# MB128_tester_PCB.net
KiCad netlist of a schematic drawn in EAGLE
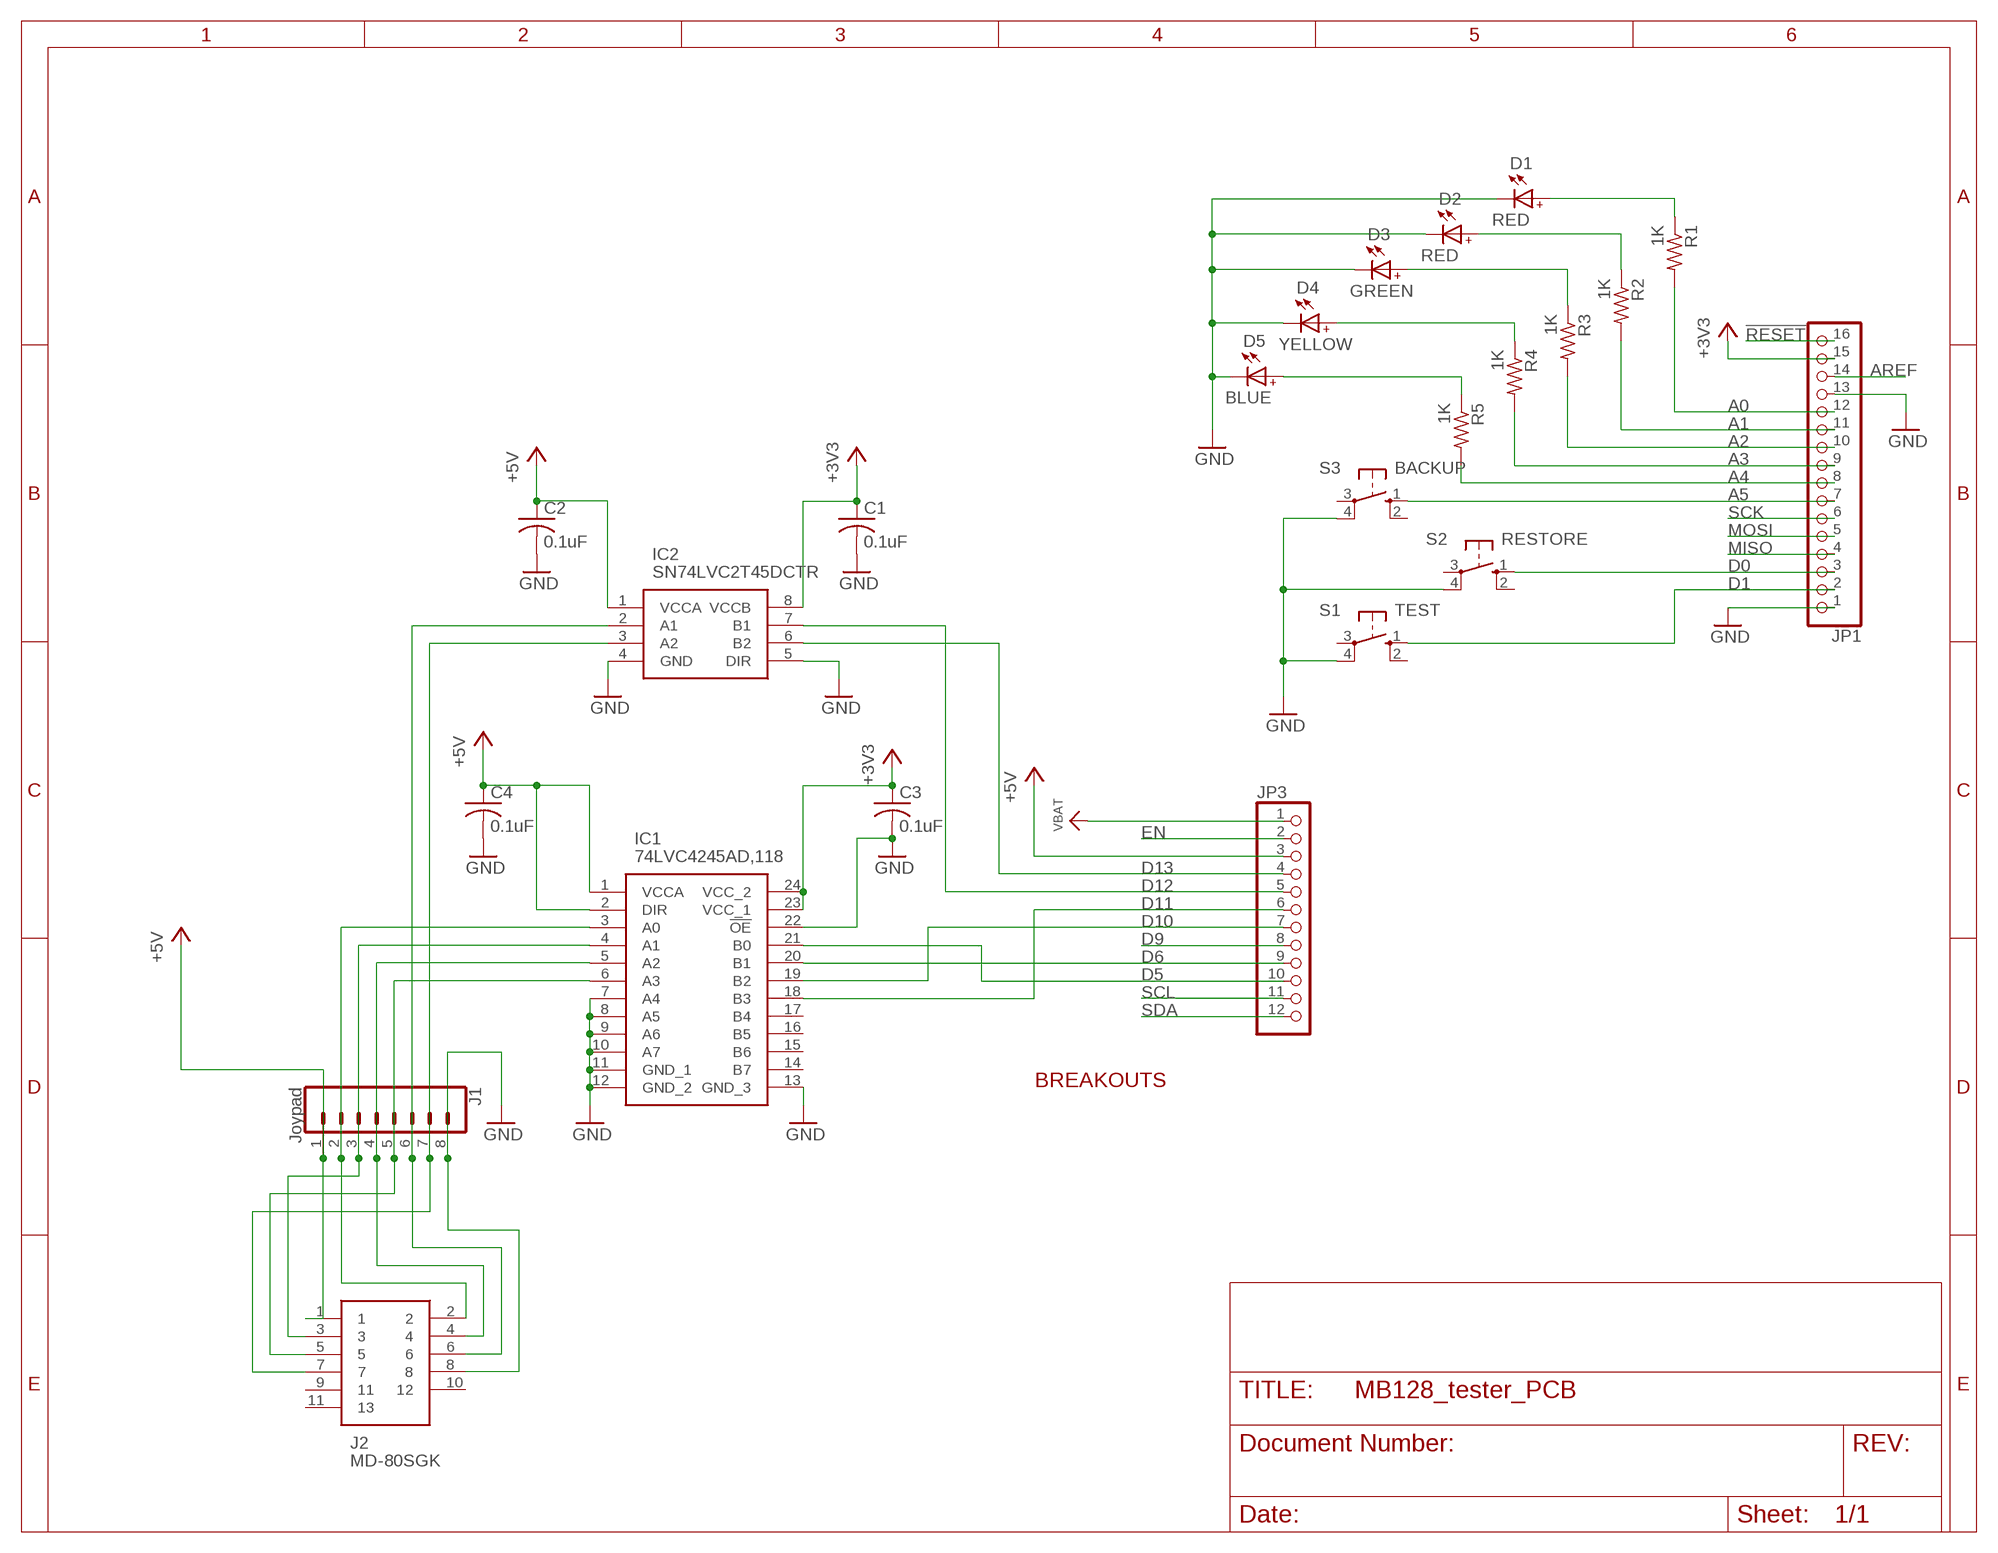
[diagram p0: schematic, sheet 1]

(export (version "E")
  (design (tool "Eeschema 10.0.6"))
  (components
    (comp (ref "C1")
      (value "0.1uF")
      (footprint "eagle-import:C0805")
      (libsource (lib "eagle-import") (part "C-USC0805"))
    )
    (comp (ref "C2")
      (value "0.1uF")
      (footprint "eagle-import:C0805")
      (libsource (lib "eagle-import") (part "C-USC0805"))
    )
    (comp (ref "C3")
      (value "0.1uF")
      (footprint "eagle-import:C0805")
      (libsource (lib "eagle-import") (part "C-USC0805"))
    )
    (comp (ref "C4")
      (value "0.1uF")
      (footprint "eagle-import:C0805")
      (libsource (lib "eagle-import") (part "C-USC0805"))
    )
    (comp (ref "D1")
      (value "RED")
      (footprint "eagle-import:WL-SMCC_0603_R_Y_V")
      (libsource (lib "eagle-import") (part "WL-SMCC_0603_R/V/Y_150060RS73220"))
    )
    (comp (ref "D2")
      (value "RED")
      (footprint "eagle-import:WL-SMCC_0603_R_Y_V")
      (libsource (lib "eagle-import") (part "WL-SMCC_0603_R/V/Y_150060RS73220"))
    )
    (comp (ref "D3")
      (value "GREEN")
      (footprint "eagle-import:WL-SMCC_0603_R_Y_V")
      (libsource (lib "eagle-import") (part "WL-SMCC_0603_R/V/Y_150060RS73220"))
    )
    (comp (ref "D4")
      (value "YELLOW")
      (footprint "eagle-import:WL-SMCC_0603_R_Y_V")
      (libsource (lib "eagle-import") (part "WL-SMCC_0603_R/V/Y_150060RS73220"))
    )
    (comp (ref "D5")
      (value "BLUE")
      (footprint "eagle-import:WL-SMCC_0603_R_Y_V")
      (libsource (lib "eagle-import") (part "WL-SMCC_0603_R/V/Y_150060RS73220"))
    )
    (comp (ref "IC1")
      (value "74LVC4245AD,118")
      (footprint "eagle-import:SOIC127P1032X265-24N")
      (fields
        (field (name "MOUSER_PART_NUMBER") "771-74LVC4245AD-T")
        (field (name "RS_PART_NUMBER") "1708039")
      )
      (libsource (lib "eagle-import") (part "74LVC4245AD,118"))
    )
    (comp (ref "IC2")
      (value "SN74LVC2T45DCTR")
      (footprint "eagle-import:SOP65P400X130-8N")
      (fields
        (field (name "MOUSER_PART_NUMBER") "595-SN74LVC2T45DCTR")
        (field (name "RS_PART_NUMBER") "9213022")
      )
      (libsource (lib "eagle-import") (part "SN74LVC2T45DCTR"))
    )
    (comp (ref "J1")
      (value "Joypad")
      (footprint "eagle-import:1X08")
      (libsource (lib "eagle-import") (part "CONN_08{dblquote}"))
    )
    (comp (ref "J2")
      (value "MD-80SGK")
      (footprint "eagle-import:MD80SGK")
      (fields (field (name "MOUSER_PART_NUMBER") "490-MD-80SGK"))
      (libsource (lib "eagle-import") (part "MD-80SGK"))
    )
    (comp (ref "JP1")
      (value "HEADER-1X16ROUND")
      (footprint "eagle-import:1X16_ROUND")
      (libsource (lib "eagle-import") (part "HEADER-1X16ROUND"))
    )
    (comp (ref "JP3")
      (value "HEADER-1X12")
      (footprint "eagle-import:1X12_ROUND")
      (libsource (lib "eagle-import") (part "HEADER-1X12"))
    )
    (comp (ref "R1")
      (value "1K")
      (footprint "eagle-import:R0603")
      (libsource (lib "eagle-import") (part "R-US_R0603"))
    )
    (comp (ref "R2")
      (value "1K")
      (footprint "eagle-import:R0603")
      (libsource (lib "eagle-import") (part "R-US_R0603"))
    )
    (comp (ref "R3")
      (value "1K")
      (footprint "eagle-import:R0603")
      (libsource (lib "eagle-import") (part "R-US_R0603"))
    )
    (comp (ref "R4")
      (value "1K")
      (footprint "eagle-import:R0603")
      (libsource (lib "eagle-import") (part "R-US_R0603"))
    )
    (comp (ref "R5")
      (value "1K")
      (footprint "eagle-import:R0603")
      (libsource (lib "eagle-import") (part "R-US_R0603"))
    )
    (comp (ref "S1")
      (value "TEST")
      (footprint "eagle-import:B3F-10XX")
      (fields (field (name "MPN") "B3F-1000"))
      (libsource (lib "eagle-import") (part "10-XX"))
    )
    (comp (ref "S2")
      (value "RESTORE")
      (footprint "eagle-import:B3F-10XX")
      (fields (field (name "MPN") "B3F-1000"))
      (libsource (lib "eagle-import") (part "10-XX"))
    )
    (comp (ref "S3")
      (value "BACKUP")
      (footprint "eagle-import:B3F-10XX")
      (fields (field (name "MPN") "B3F-1000"))
      (libsource (lib "eagle-import") (part "10-XX"))
    )
  )
  (nets
    (net (code "1") (name "+3V3") (class "Default")
      (node (ref "C1") (pin "1") (pinfunction "1_1") (pintype "passive"))
      (node (ref "C3") (pin "1") (pinfunction "1_1") (pintype "passive"))
      (node (ref "IC1") (pin "23") (pinfunction "VCC_1_23") (pintype "bidirectional"))
      (node (ref "IC1") (pin "24") (pinfunction "VCC_2_24") (pintype "bidirectional"))
      (node (ref "IC2") (pin "8") (pinfunction "VCCB_8") (pintype "power_in"))
      (node (ref "JP1") (pin "15") (pinfunction "15_15") (pintype "passive"))
    )
    (net (code "2") (name "+5V") (class "Default")
      (node (ref "C2") (pin "1") (pinfunction "1_1") (pintype "passive"))
      (node (ref "C4") (pin "1") (pinfunction "1_1") (pintype "passive"))
      (node (ref "IC1") (pin "1") (pinfunction "VCCA_1") (pintype "bidirectional"))
      (node (ref "IC1") (pin "2") (pinfunction "DIR_2") (pintype "bidirectional"))
      (node (ref "IC2") (pin "1") (pinfunction "VCCA_1") (pintype "power_in"))
      (node (ref "J1") (pin "1") (pinfunction "1_1") (pintype "passive"))
      (node (ref "J2") (pin "1") (pinfunction "1_1") (pintype "bidirectional"))
      (node (ref "JP3") (pin "3") (pinfunction "3_3") (pintype "passive"))
    )
    (net (code "3") (name "/A0") (class "Default")
      (node (ref "JP1") (pin "12") (pinfunction "12_12") (pintype "passive"))
      (node (ref "R1") (pin "2") (pinfunction "2_2") (pintype "passive"))
    )
    (net (code "4") (name "/A1") (class "Default")
      (node (ref "JP1") (pin "11") (pinfunction "11_11") (pintype "passive"))
      (node (ref "R2") (pin "2") (pinfunction "2_2") (pintype "passive"))
    )
    (net (code "5") (name "/A2") (class "Default")
      (node (ref "JP1") (pin "10") (pinfunction "10_10") (pintype "passive"))
      (node (ref "R3") (pin "2") (pinfunction "2_2") (pintype "passive"))
    )
    (net (code "6") (name "/A3") (class "Default")
      (node (ref "JP1") (pin "9") (pinfunction "9_9") (pintype "passive"))
      (node (ref "R4") (pin "2") (pinfunction "2_2") (pintype "passive"))
    )
    (net (code "7") (name "/A4") (class "Default")
      (node (ref "JP1") (pin "8") (pinfunction "8_8") (pintype "passive"))
      (node (ref "R5") (pin "2") (pinfunction "2_2") (pintype "passive"))
    )
    (net (code "8") (name "/A5") (class "Default")
      (node (ref "JP1") (pin "7") (pinfunction "7_7") (pintype "passive"))
      (node (ref "S3") (pin "1") (pinfunction "S_1") (pintype "passive"))
    )
    (net (code "9") (name "/AREF") (class "Default")
      (node (ref "JP1") (pin "14") (pinfunction "14_14") (pintype "passive"))
    )
    (net (code "10") (name "/D0") (class "Default")
      (node (ref "JP1") (pin "3") (pinfunction "3_3") (pintype "passive"))
      (node (ref "S2") (pin "1") (pinfunction "S_1") (pintype "passive"))
    )
    (net (code "11") (name "/D1") (class "Default")
      (node (ref "JP1") (pin "2") (pinfunction "2_2") (pintype "passive"))
      (node (ref "S1") (pin "1") (pinfunction "S_1") (pintype "passive"))
    )
    (net (code "12") (name "/D5") (class "Default")
      (node (ref "IC1") (pin "21") (pinfunction "B0_21") (pintype "bidirectional"))
      (node (ref "JP3") (pin "10") (pinfunction "10_10") (pintype "passive"))
    )
    (net (code "13") (name "/D6") (class "Default")
      (node (ref "IC1") (pin "20") (pinfunction "B1_20") (pintype "bidirectional"))
      (node (ref "JP3") (pin "9") (pinfunction "9_9") (pintype "passive"))
    )
    (net (code "14") (name "/D9") (class "Default")
      (node (ref "JP3") (pin "8") (pinfunction "8_8") (pintype "passive"))
    )
    (net (code "15") (name "/D10") (class "Default")
      (node (ref "IC1") (pin "19") (pinfunction "B2_19") (pintype "bidirectional"))
      (node (ref "JP3") (pin "7") (pinfunction "7_7") (pintype "passive"))
    )
    (net (code "16") (name "/D11") (class "Default")
      (node (ref "IC1") (pin "18") (pinfunction "B3_18") (pintype "bidirectional"))
      (node (ref "JP3") (pin "6") (pinfunction "6_6") (pintype "passive"))
    )
    (net (code "17") (name "/D12") (class "Default")
      (node (ref "IC2") (pin "7") (pinfunction "B1_7") (pintype "bidirectional"))
      (node (ref "JP3") (pin "5") (pinfunction "5_5") (pintype "passive"))
    )
    (net (code "18") (name "/D13") (class "Default")
      (node (ref "IC2") (pin "6") (pinfunction "B2_6") (pintype "bidirectional"))
      (node (ref "JP3") (pin "4") (pinfunction "4_4") (pintype "passive"))
    )
    (net (code "19") (name "/EN") (class "Default")
      (node (ref "JP3") (pin "2") (pinfunction "2_2") (pintype "passive"))
    )
    (net (code "20") (name "/MISO") (class "Default")
      (node (ref "JP1") (pin "4") (pinfunction "4_4") (pintype "passive"))
    )
    (net (code "21") (name "/MOSI") (class "Default")
      (node (ref "JP1") (pin "5") (pinfunction "5_5") (pintype "passive"))
    )
    (net (code "22") (name "/SCK") (class "Default")
      (node (ref "JP1") (pin "6") (pinfunction "6_6") (pintype "passive"))
    )
    (net (code "23") (name "/SCL") (class "Default")
      (node (ref "JP3") (pin "11") (pinfunction "11_11") (pintype "passive"))
    )
    (net (code "24") (name "/SDA") (class "Default")
      (node (ref "JP3") (pin "12") (pinfunction "12_12") (pintype "passive"))
    )
    (net (code "25") (name "/~{RESET}") (class "Default")
      (node (ref "JP1") (pin "16") (pinfunction "16_16") (pintype "passive"))
    )
    (net (code "26") (name "GND") (class "Default")
      (node (ref "C1") (pin "2") (pinfunction "2_2") (pintype "passive"))
      (node (ref "C2") (pin "2") (pinfunction "2_2") (pintype "passive"))
      (node (ref "C3") (pin "2") (pinfunction "2_2") (pintype "passive"))
      (node (ref "C4") (pin "2") (pinfunction "2_2") (pintype "passive"))
      (node (ref "D1") (pin "1") (pinfunction "C_1") (pintype "passive"))
      (node (ref "D2") (pin "1") (pinfunction "C_1") (pintype "passive"))
      (node (ref "D3") (pin "1") (pinfunction "C_1") (pintype "passive"))
      (node (ref "D4") (pin "1") (pinfunction "C_1") (pintype "passive"))
      (node (ref "D5") (pin "1") (pinfunction "C_1") (pintype "passive"))
      (node (ref "IC1") (pin "10") (pinfunction "A7_10") (pintype "bidirectional"))
      (node (ref "IC1") (pin "11") (pinfunction "GND_1_11") (pintype "bidirectional"))
      (node (ref "IC1") (pin "12") (pinfunction "GND_2_12") (pintype "bidirectional"))
      (node (ref "IC1") (pin "13") (pinfunction "GND_3_13") (pintype "bidirectional"))
      (node (ref "IC1") (pin "22") (pinfunction "~{OE}_22") (pintype "bidirectional"))
      (node (ref "IC1") (pin "7") (pinfunction "A4_7") (pintype "bidirectional"))
      (node (ref "IC1") (pin "8") (pinfunction "A5_8") (pintype "bidirectional"))
      (node (ref "IC1") (pin "9") (pinfunction "A6_9") (pintype "bidirectional"))
      (node (ref "IC2") (pin "4") (pinfunction "GND_4") (pintype "power_in"))
      (node (ref "IC2") (pin "5") (pinfunction "DIR_5") (pintype "bidirectional"))
      (node (ref "J1") (pin "8") (pinfunction "8_8") (pintype "passive"))
      (node (ref "J2") (pin "8") (pinfunction "8_8") (pintype "bidirectional"))
      (node (ref "JP1") (pin "1") (pinfunction "1_1") (pintype "passive"))
      (node (ref "JP1") (pin "13") (pinfunction "13_13") (pintype "passive"))
      (node (ref "S1") (pin "4") (pinfunction "P1_4") (pintype "passive"))
      (node (ref "S2") (pin "4") (pinfunction "P1_4") (pintype "passive"))
      (node (ref "S3") (pin "4") (pinfunction "P1_4") (pintype "passive"))
    )
    (net (code "27") (name "Net-(D1-A)") (class "Default")
      (node (ref "D1") (pin "2") (pinfunction "A_2") (pintype "passive"))
      (node (ref "R1") (pin "1") (pinfunction "1_1") (pintype "passive"))
    )
    (net (code "28") (name "Net-(D2-A)") (class "Default")
      (node (ref "D2") (pin "2") (pinfunction "A_2") (pintype "passive"))
      (node (ref "R2") (pin "1") (pinfunction "1_1") (pintype "passive"))
    )
    (net (code "29") (name "Net-(D3-A)") (class "Default")
      (node (ref "D3") (pin "2") (pinfunction "A_2") (pintype "passive"))
      (node (ref "R3") (pin "1") (pinfunction "1_1") (pintype "passive"))
    )
    (net (code "30") (name "Net-(D4-A)") (class "Default")
      (node (ref "D4") (pin "2") (pinfunction "A_2") (pintype "passive"))
      (node (ref "R4") (pin "1") (pinfunction "1_1") (pintype "passive"))
    )
    (net (code "31") (name "Net-(D5-A)") (class "Default")
      (node (ref "D5") (pin "2") (pinfunction "A_2") (pintype "passive"))
      (node (ref "R5") (pin "1") (pinfunction "1_1") (pintype "passive"))
    )
    (net (code "32") (name "Net-(IC1-A0)") (class "Default")
      (node (ref "IC1") (pin "3") (pinfunction "A0_3") (pintype "bidirectional"))
      (node (ref "J1") (pin "2") (pinfunction "2_2") (pintype "passive"))
      (node (ref "J2") (pin "2") (pinfunction "2_2") (pintype "bidirectional"))
    )
    (net (code "33") (name "Net-(IC1-A1)") (class "Default")
      (node (ref "IC1") (pin "4") (pinfunction "A1_4") (pintype "bidirectional"))
      (node (ref "J1") (pin "3") (pinfunction "3_3") (pintype "passive"))
      (node (ref "J2") (pin "3") (pinfunction "3_3") (pintype "bidirectional"))
    )
    (net (code "34") (name "Net-(IC1-A2)") (class "Default")
      (node (ref "IC1") (pin "5") (pinfunction "A2_5") (pintype "bidirectional"))
      (node (ref "J1") (pin "4") (pinfunction "4_4") (pintype "passive"))
      (node (ref "J2") (pin "4") (pinfunction "4_4") (pintype "bidirectional"))
    )
    (net (code "35") (name "Net-(IC1-A3)") (class "Default")
      (node (ref "IC1") (pin "6") (pinfunction "A3_6") (pintype "bidirectional"))
      (node (ref "J1") (pin "5") (pinfunction "5_5") (pintype "passive"))
      (node (ref "J2") (pin "5") (pinfunction "5_5") (pintype "bidirectional"))
    )
    (net (code "36") (name "Net-(IC2-A1)") (class "Default")
      (node (ref "IC2") (pin "2") (pinfunction "A1_2") (pintype "bidirectional"))
      (node (ref "J1") (pin "6") (pinfunction "6_6") (pintype "passive"))
      (node (ref "J2") (pin "6") (pinfunction "6_6") (pintype "bidirectional"))
    )
    (net (code "37") (name "Net-(IC2-A2)") (class "Default")
      (node (ref "IC2") (pin "3") (pinfunction "A2_3") (pintype "bidirectional"))
      (node (ref "J1") (pin "7") (pinfunction "7_7") (pintype "passive"))
      (node (ref "J2") (pin "7") (pinfunction "7_7") (pintype "bidirectional"))
    )
    (net (code "38") (name "VBAT") (class "Default")
      (node (ref "JP3") (pin "1") (pinfunction "1_1") (pintype "passive"))
    )
    (net (code "39") (name "unconnected-(IC1-B4-Pad17)") (class "Default")
      (node (ref "IC1") (pin "17") (pinfunction "B4_17") (pintype "bidirectional"))
    )
    (net (code "40") (name "unconnected-(IC1-B5-Pad16)") (class "Default")
      (node (ref "IC1") (pin "16") (pinfunction "B5_16") (pintype "bidirectional"))
    )
    (net (code "41") (name "unconnected-(IC1-B6-Pad15)") (class "Default")
      (node (ref "IC1") (pin "15") (pinfunction "B6_15") (pintype "bidirectional"))
    )
    (net (code "42") (name "unconnected-(IC1-B7-Pad14)") (class "Default")
      (node (ref "IC1") (pin "14") (pinfunction "B7_14") (pintype "bidirectional"))
    )
    (net (code "43") (name "unconnected-(J2-11-Pad9)") (class "Default")
      (node (ref "J2") (pin "9") (pinfunction "11_9") (pintype "bidirectional"))
    )
    (net (code "44") (name "unconnected-(J2-12-Pad10)") (class "Default")
      (node (ref "J2") (pin "10") (pinfunction "12_10") (pintype "bidirectional"))
    )
    (net (code "45") (name "unconnected-(J2-13-Pad11)") (class "Default")
      (node (ref "J2") (pin "11") (pinfunction "13_11") (pintype "bidirectional"))
    )
    (net (code "46") (name "unconnected-(S1-P-Pad3)") (class "Default")
      (node (ref "S1") (pin "3") (pinfunction "P_3") (pintype "passive"))
    )
    (net (code "47") (name "unconnected-(S1-S1-Pad2)") (class "Default")
      (node (ref "S1") (pin "2") (pinfunction "S1_2") (pintype "passive"))
    )
    (net (code "48") (name "unconnected-(S2-P-Pad3)") (class "Default")
      (node (ref "S2") (pin "3") (pinfunction "P_3") (pintype "passive"))
    )
    (net (code "49") (name "unconnected-(S2-S1-Pad2)") (class "Default")
      (node (ref "S2") (pin "2") (pinfunction "S1_2") (pintype "passive"))
    )
    (net (code "50") (name "unconnected-(S3-P-Pad3)") (class "Default")
      (node (ref "S3") (pin "3") (pinfunction "P_3") (pintype "passive"))
    )
    (net (code "51") (name "unconnected-(S3-S1-Pad2)") (class "Default")
      (node (ref "S3") (pin "2") (pinfunction "S1_2") (pintype "passive"))
    )
  )
)
